# Module.net
KiCad netlist of a schematic drawn in Altium Designer
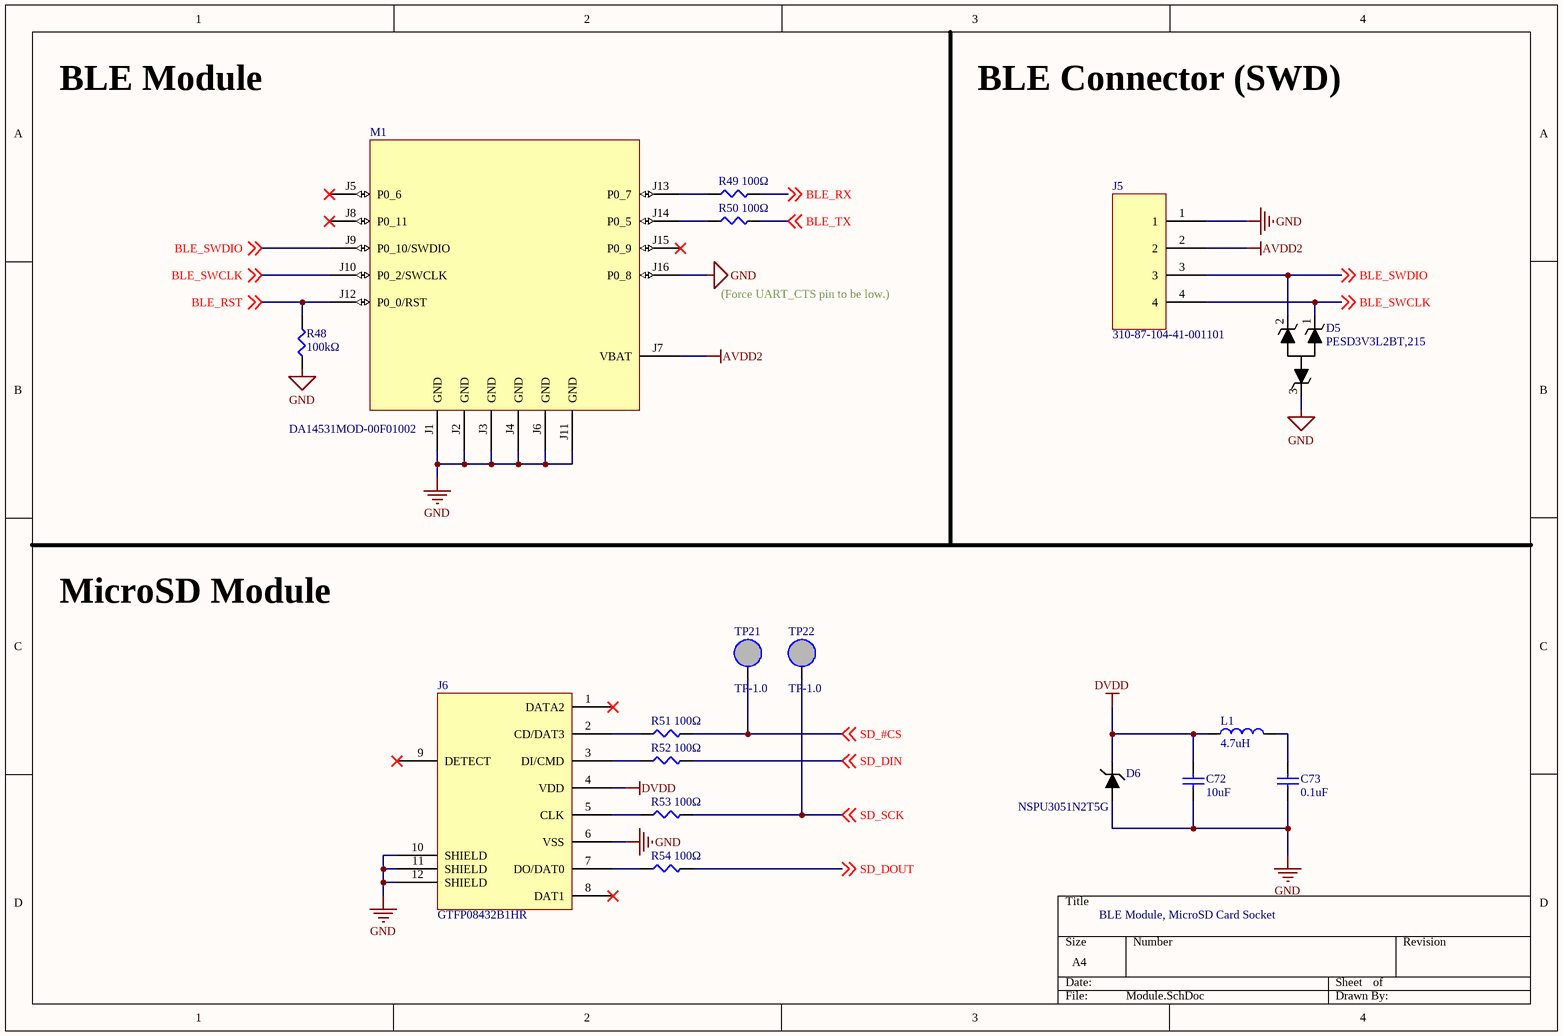
[diagram p0: Module.SchDoc]

(export (version "E")
  (design (tool "Eeschema 10.0.6"))
  (components
    (comp (ref "C72")
      (value "10uF")
      (footprint "0603")
      (description "MLCC-0603")
      (libsource (lib "MLCC") (part "0603"))
    )
    (comp (ref "C73")
      (value "0.1uF")
      (footprint "0402")
      (description "MLCC-0402")
      (libsource (lib "MLCC") (part "0402"))
    )
    (comp (ref "D5")
      (value "PESD3V3L2BT,215")
      (footprint "SOT-23-3")
      (description "ESD Suppressors / TVS Diodes, 2 Channl. Breakdown 6.4V, Clamping Voltage 8V")
      (libsource (lib "PESDxL2BT") (part "PESD3V3L2BT,215"))
    )
    (comp (ref "D6")
      (value "NSPU3051N2T5G")
      (footprint "X2DFN-2(0.73-0.6x1.0x0.37)")
      (description "0016-11-ESD-01-D3V3F4U10LP-7")
      (fields (field (name "AUTHORBY") "yjlab"))
      (libsource (lib "NSPU3051") (part "NSPU3051N2T5G"))
    )
    (comp (ref "J5")
      (value "310-87-104-41-001101")
      (footprint "4Pos, 1Row")
      (description "Headers & Wire Housings, Through Hole, 4 Poisition, 1 Row, Straight, Pitch 2.54 mm")
      (libsource (lib "310-xx-1xx-41-001101") (part "310-87-104-41-001101"))
    )
    (comp (ref "J6")
      (value "GTFP08432B1HR")
      (footprint "microSD_Card_slot")
      (description "0023-23-MMC-02-GTFP08432B1HR")
      (libsource (lib "GTFP08432B1HR") (part "GTFP08432B1HR"))
    )
    (comp (ref "L1")
      (value "4.7uH")
      (footprint "3.2 mm x 2.5 mm x 1 mm")
      (description "SRP3212 Series Shielded Power Inductors, Wirewound")
      (libsource (lib "SRP3212") (part "SRP3212"))
    )
    (comp (ref "M1")
      (value "DA14531MOD-00F01002")
      (footprint "DA14531MOD-00F01002")
      (description "0038-15-BLT-07-DA14531MOD-00F01002")
      (libsource (lib "DA14531MOD") (part "DA14531MOD-00F01002"))
    )
    (comp (ref "R48")
      (value "100kΩ")
      (footprint "0402")
      (description "Resistor_SMD_0402")
      (fields (field (name "AUTHORBY") "yjlab"))
      (libsource (lib "Resistor") (part "0402"))
    )
    (comp (ref "R49")
      (value "100Ω")
      (footprint "0402")
      (description "Resistor_SMD_0402")
      (fields (field (name "AUTHORBY") "yjlab"))
      (libsource (lib "Resistor") (part "0402"))
    )
    (comp (ref "R50")
      (value "100Ω")
      (footprint "0402")
      (description "Resistor_SMD_0402")
      (fields (field (name "AUTHORBY") "yjlab"))
      (libsource (lib "Resistor") (part "0402"))
    )
    (comp (ref "R51")
      (value "100Ω")
      (footprint "0402")
      (description "Resistor_SMD_0402")
      (fields (field (name "AUTHORBY") "yjlab"))
      (libsource (lib "Resistor") (part "0402"))
    )
    (comp (ref "R52")
      (value "100Ω")
      (footprint "0402")
      (description "Resistor_SMD_0402")
      (fields (field (name "AUTHORBY") "yjlab"))
      (libsource (lib "Resistor") (part "0402"))
    )
    (comp (ref "R53")
      (value "100Ω")
      (footprint "0402")
      (description "Resistor_SMD_0402")
      (fields (field (name "AUTHORBY") "yjlab"))
      (libsource (lib "Resistor") (part "0402"))
    )
    (comp (ref "R54")
      (value "100Ω")
      (footprint "0402")
      (description "Resistor_SMD_0402")
      (fields (field (name "AUTHORBY") "yjlab"))
      (libsource (lib "Resistor") (part "0402"))
    )
    (comp (ref "TP21")
      (value "TP-1.0")
      (footprint "Testpoint")
      (libsource (lib "Testpoint") (part "Testpoint"))
    )
    (comp (ref "TP22")
      (value "TP-1.0")
      (footprint "Testpoint")
      (libsource (lib "Testpoint") (part "Testpoint"))
    )
  )
  (nets
    (net (code "1") (name "AVDD2") (class "Default")
      (node (ref "J5") (pin "2") (pinfunction "2_2") (pintype "passive"))
      (node (ref "M1") (pin "J7") (pinfunction "VBAT_J7") (pintype "passive"))
    )
    (net (code "2") (name "BLE_RST") (class "Default")
      (node (ref "M1") (pin "J12") (pinfunction "P0_0/RST_J12") (pintype "bidirectional"))
      (node (ref "R48") (pin "2") (pinfunction "2_2") (pintype "passive"))
    )
    (net (code "3") (name "BLE_RX") (class "Default")
      (node (ref "R49") (pin "2") (pinfunction "2_2") (pintype "passive"))
    )
    (net (code "4") (name "BLE_SWCLK") (class "Default")
      (node (ref "D5") (pin "1") (pinfunction "1_1") (pintype "passive"))
      (node (ref "J5") (pin "4") (pinfunction "4_4") (pintype "passive"))
      (node (ref "M1") (pin "J10") (pinfunction "P0_2/SWCLK_J10") (pintype "bidirectional"))
    )
    (net (code "5") (name "BLE_SWDIO") (class "Default")
      (node (ref "D5") (pin "2") (pinfunction "2_2") (pintype "passive"))
      (node (ref "J5") (pin "3") (pinfunction "3_3") (pintype "passive"))
      (node (ref "M1") (pin "J9") (pinfunction "P0_10/SWDIO_J9") (pintype "bidirectional"))
    )
    (net (code "6") (name "BLE_TX") (class "Default")
      (node (ref "R50") (pin "2") (pinfunction "2_2") (pintype "passive"))
    )
    (net (code "7") (name "DVDD") (class "Default")
      (node (ref "C72") (pin "2") (pinfunction "2_2") (pintype "passive"))
      (node (ref "D6") (pin "1") (pinfunction "CATHODE_1") (pintype "passive"))
      (node (ref "J6") (pin "4") (pinfunction "VDD_4") (pintype "passive"))
      (node (ref "L1") (pin "1") (pinfunction "1_1") (pintype "passive"))
    )
    (net (code "8") (name "GND") (class "Default")
      (node (ref "C72") (pin "1") (pinfunction "1_1") (pintype "passive"))
      (node (ref "C73") (pin "1") (pinfunction "1_1") (pintype "passive"))
      (node (ref "D5") (pin "3") (pinfunction "3_3") (pintype "passive"))
      (node (ref "D6") (pin "2") (pinfunction "ANODE_2") (pintype "passive"))
      (node (ref "J5") (pin "1") (pinfunction "1_1") (pintype "passive"))
      (node (ref "J6") (pin "10") (pinfunction "SHIELD_10") (pintype "passive"))
      (node (ref "J6") (pin "11") (pinfunction "SHIELD_11") (pintype "passive"))
      (node (ref "J6") (pin "12") (pinfunction "SHIELD_12") (pintype "passive"))
      (node (ref "J6") (pin "6") (pinfunction "VSS_6") (pintype "passive"))
      (node (ref "M1") (pin "J1") (pinfunction "GND_J1") (pintype "passive"))
      (node (ref "M1") (pin "J11") (pinfunction "GND_J11") (pintype "passive"))
      (node (ref "M1") (pin "J16") (pinfunction "P0_8_J16") (pintype "bidirectional"))
      (node (ref "M1") (pin "J2") (pinfunction "GND_J2") (pintype "passive"))
      (node (ref "M1") (pin "J3") (pinfunction "GND_J3") (pintype "passive"))
      (node (ref "M1") (pin "J4") (pinfunction "GND_J4") (pintype "passive"))
      (node (ref "M1") (pin "J6") (pinfunction "GND_J6") (pintype "passive"))
      (node (ref "R48") (pin "1") (pinfunction "1_1") (pintype "passive"))
    )
    (net (code "9") (name "Net-(C73-Pad2)") (class "Default")
      (node (ref "C73") (pin "2") (pinfunction "2_2") (pintype "passive"))
      (node (ref "L1") (pin "2") (pinfunction "2_2") (pintype "passive"))
    )
    (net (code "10") (name "Net-(J6-CD{slash}DAT3)") (class "Default")
      (node (ref "J6") (pin "2") (pinfunction "CD/DAT3_2") (pintype "passive"))
      (node (ref "R51") (pin "1") (pinfunction "1_1") (pintype "passive"))
    )
    (net (code "11") (name "Net-(J6-CLK)") (class "Default")
      (node (ref "J6") (pin "5") (pinfunction "CLK_5") (pintype "passive"))
      (node (ref "R53") (pin "1") (pinfunction "1_1") (pintype "passive"))
    )
    (net (code "12") (name "Net-(J6-DI{slash}CMD)") (class "Default")
      (node (ref "J6") (pin "3") (pinfunction "DI/CMD_3") (pintype "passive"))
      (node (ref "R52") (pin "1") (pinfunction "1_1") (pintype "passive"))
    )
    (net (code "13") (name "Net-(J6-DO{slash}DAT0)") (class "Default")
      (node (ref "J6") (pin "7") (pinfunction "DO/DAT0_7") (pintype "passive"))
      (node (ref "R54") (pin "1") (pinfunction "1_1") (pintype "passive"))
    )
    (net (code "14") (name "Net-(M1-P0_5)") (class "Default")
      (node (ref "M1") (pin "J14") (pinfunction "P0_5_J14") (pintype "bidirectional"))
      (node (ref "R50") (pin "1") (pinfunction "1_1") (pintype "passive"))
    )
    (net (code "15") (name "Net-(M1-P0_7)") (class "Default")
      (node (ref "M1") (pin "J13") (pinfunction "P0_7_J13") (pintype "bidirectional"))
      (node (ref "R49") (pin "1") (pinfunction "1_1") (pintype "passive"))
    )
    (net (code "16") (name "SD_#CS") (class "Default")
      (node (ref "R51") (pin "2") (pinfunction "2_2") (pintype "passive"))
      (node (ref "TP21") (pin "1") (pinfunction "1_1") (pintype "passive"))
    )
    (net (code "17") (name "SD_DIN") (class "Default")
      (node (ref "R52") (pin "2") (pinfunction "2_2") (pintype "passive"))
    )
    (net (code "18") (name "SD_DOUT") (class "Default")
      (node (ref "R54") (pin "2") (pinfunction "2_2") (pintype "passive"))
    )
    (net (code "19") (name "SD_SCK") (class "Default")
      (node (ref "R53") (pin "2") (pinfunction "2_2") (pintype "passive"))
      (node (ref "TP22") (pin "1") (pinfunction "1_1") (pintype "passive"))
    )
    (net (code "20") (name "unconnected-(J6-DAT1-Pad8)") (class "Default")
      (node (ref "J6") (pin "8") (pinfunction "DAT1_8") (pintype "passive+no_connect"))
    )
    (net (code "21") (name "unconnected-(J6-DATA2-Pad1)") (class "Default")
      (node (ref "J6") (pin "1") (pinfunction "DATA2_1") (pintype "passive+no_connect"))
    )
    (net (code "22") (name "unconnected-(J6-DETECT-Pad9)") (class "Default")
      (node (ref "J6") (pin "9") (pinfunction "DETECT_9") (pintype "passive+no_connect"))
    )
    (net (code "23") (name "unconnected-(M1-P0_6-PadJ5)") (class "Default")
      (node (ref "M1") (pin "J5") (pinfunction "P0_6_J5") (pintype "bidirectional+no_connect"))
    )
    (net (code "24") (name "unconnected-(M1-P0_9-PadJ15)") (class "Default")
      (node (ref "M1") (pin "J15") (pinfunction "P0_9_J15") (pintype "bidirectional+no_connect"))
    )
    (net (code "25") (name "unconnected-(M1-P0_11-PadJ8)") (class "Default")
      (node (ref "M1") (pin "J8") (pinfunction "P0_11_J8") (pintype "bidirectional+no_connect"))
    )
  )
)
